# AfternoonCape_RevA3_6chan.net
KiCad netlist of a schematic drawn in Altium Designer
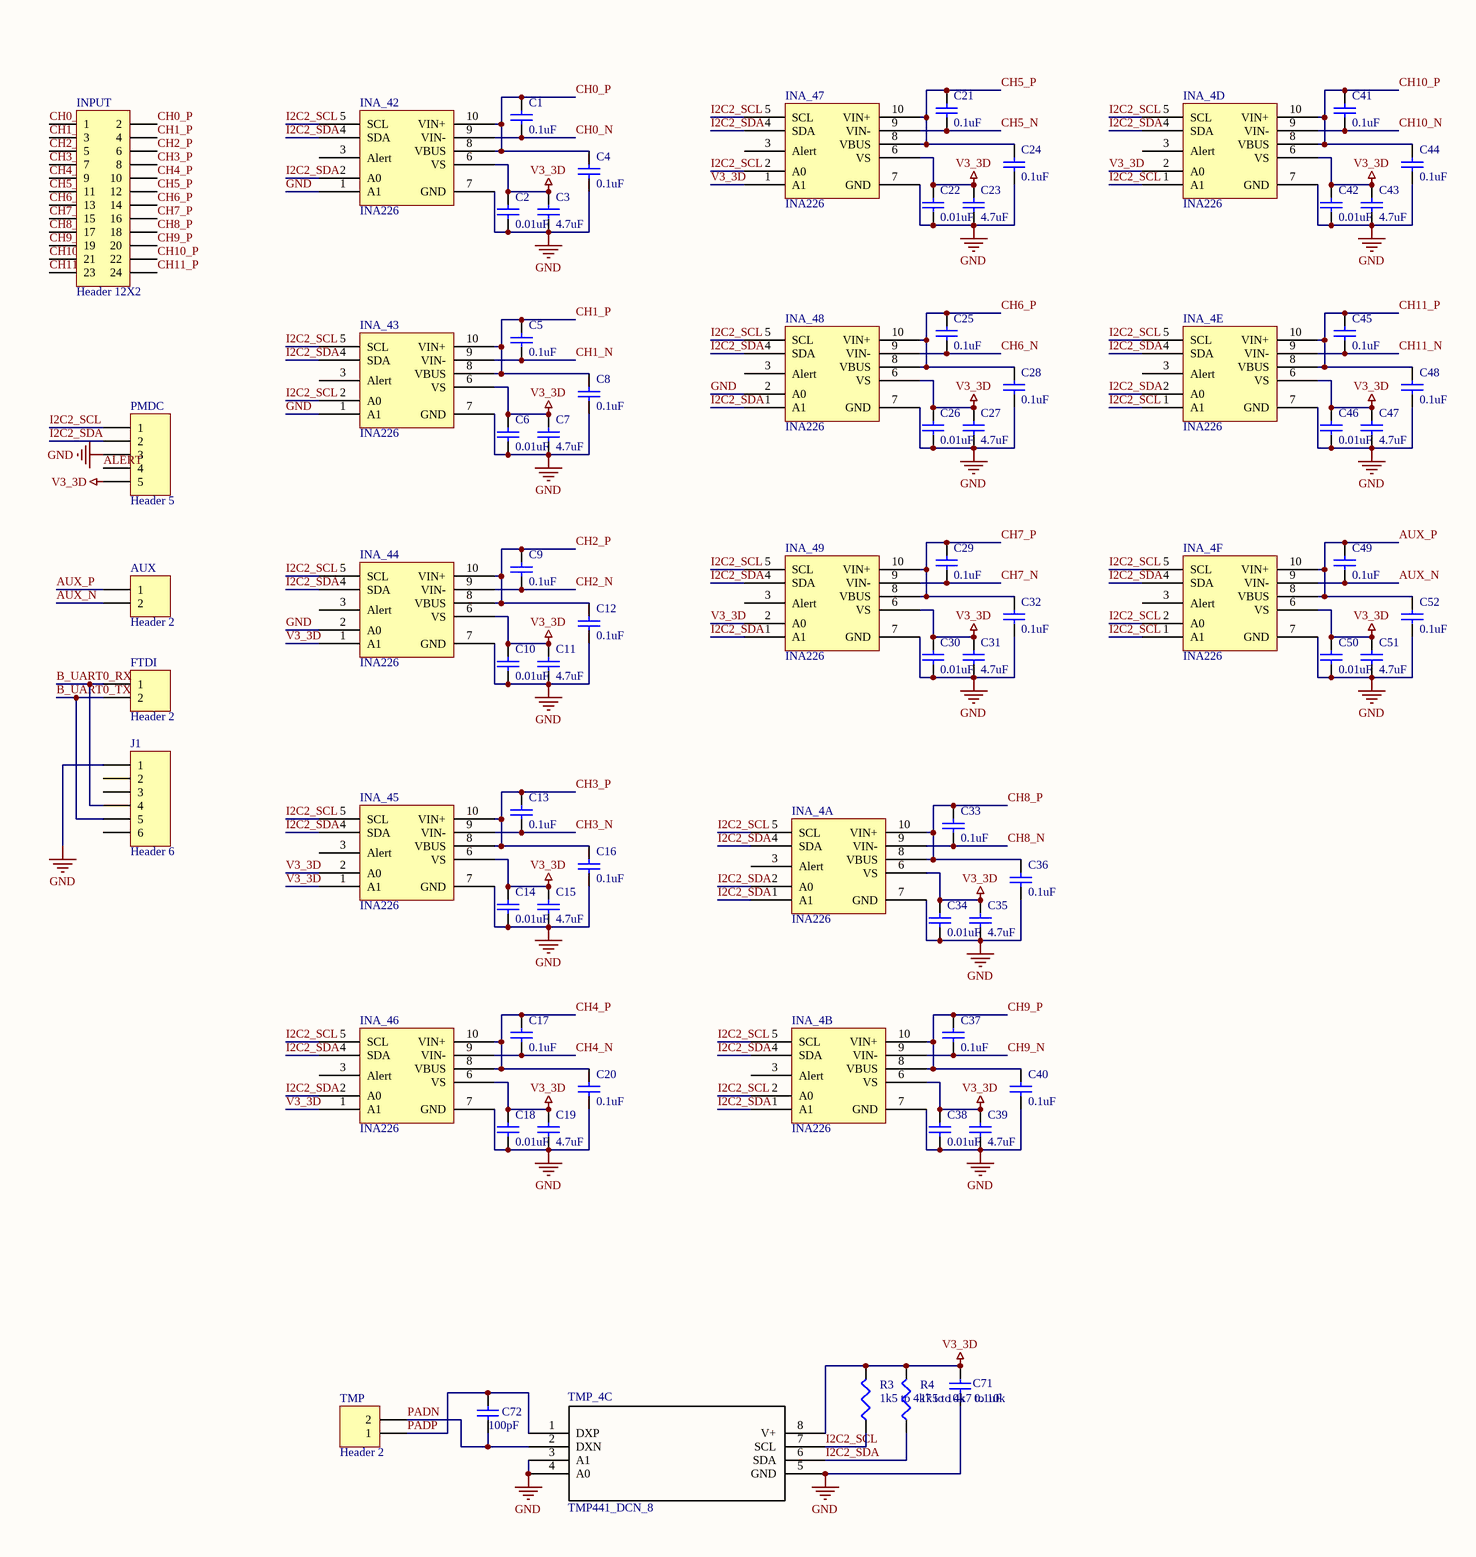
[diagram p0: AfternoonCape_RevA3_6chan.SchDoc, left]
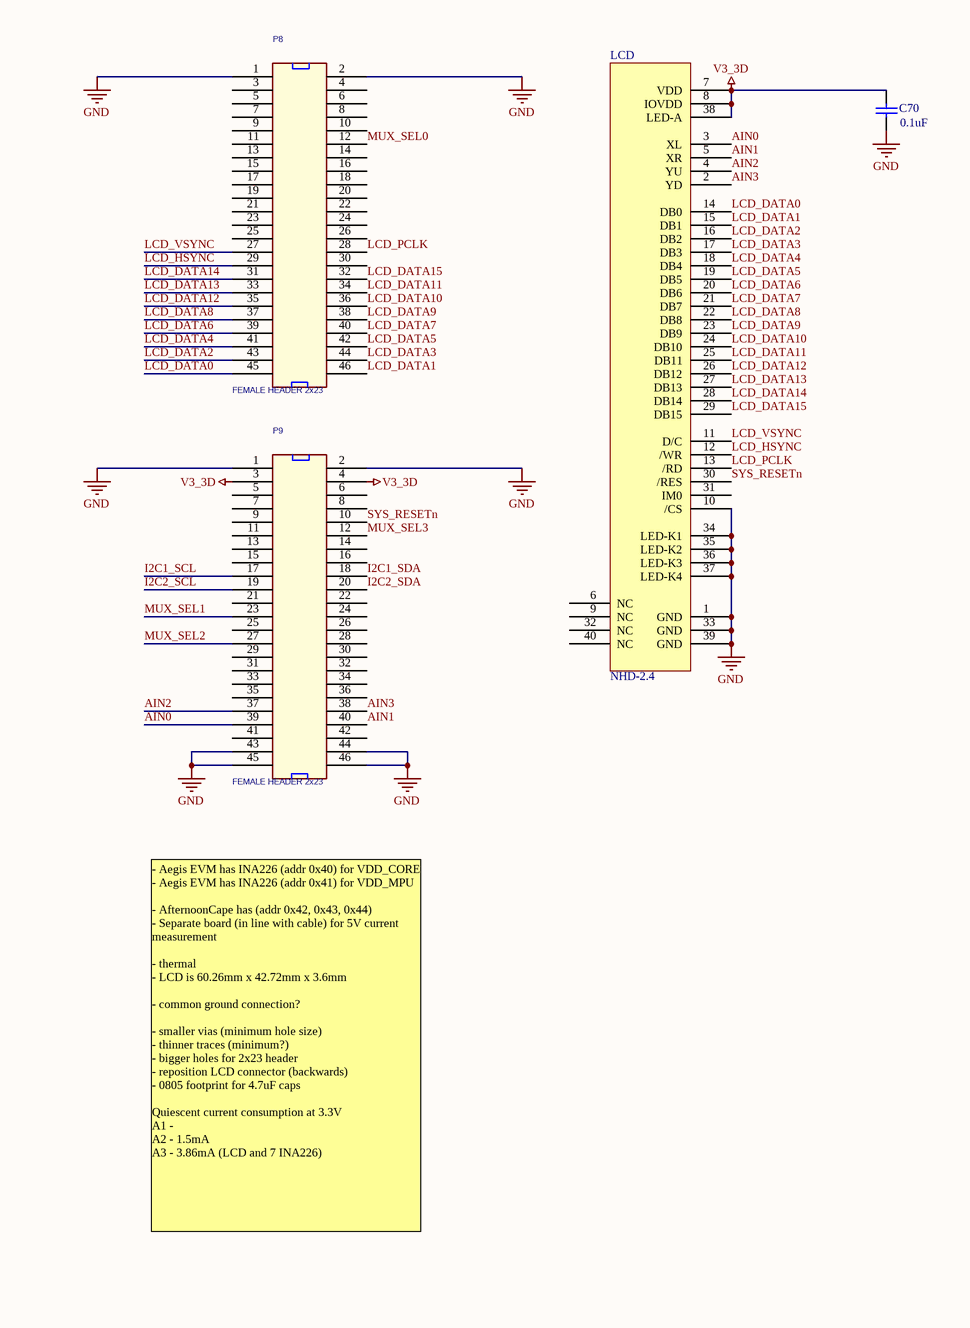
[diagram p1: AfternoonCape_RevA3_6chan.SchDoc, right]

(export (version "E")
  (design (tool "Eeschema 10.0.6"))
  (components
    (comp (ref "AUX")
      (value "Header 2")
      (footprint "HDR1X2")
      (description "Header, 2-Pin")
      (fields (field (name "PUBLISHER") "Altium Limited"))
      (libsource (lib "") (part "Header 2_1"))
    )
    (comp (ref "C1")
      (value "0.1uF")
      (footprint "0402")
      (description "Capacitor (Semiconductor SIM Model)")
      (fields (field (name "Comment") "Cap Semi") (field (name "PUBLISHER") "Altium Limited"))
      (libsource (lib "Miscellaneous Devices") (part "Cap Semi"))
    )
    (comp (ref "C2")
      (value "0.01uF")
      (footprint "0402")
      (description "Capacitor (Semiconductor SIM Model)")
      (fields (field (name "Comment") "Cap Semi") (field (name "PUBLISHER") "Altium Limited"))
      (libsource (lib "Miscellaneous Devices") (part "Cap Semi"))
    )
    (comp (ref "C3")
      (value "4.7uF")
      (footprint "0402")
      (description "Capacitor (Semiconductor SIM Model)")
      (fields (field (name "Comment") "Cap Semi") (field (name "PUBLISHER") "Altium Limited"))
      (libsource (lib "Miscellaneous Devices") (part "Cap Semi"))
    )
    (comp (ref "C4")
      (value "0.1uF")
      (footprint "0402")
      (description "Capacitor (Semiconductor SIM Model)")
      (fields (field (name "Comment") "Cap Semi") (field (name "PUBLISHER") "Altium Limited"))
      (libsource (lib "Miscellaneous Devices") (part "Cap Semi"))
    )
    (comp (ref "C5")
      (value "0.1uF")
      (footprint "0402")
      (description "Capacitor (Semiconductor SIM Model)")
      (fields (field (name "Comment") "Cap Semi") (field (name "PUBLISHER") "Altium Limited"))
      (libsource (lib "Miscellaneous Devices") (part "Cap Semi"))
    )
    (comp (ref "C6")
      (value "0.01uF")
      (footprint "0402")
      (description "Capacitor (Semiconductor SIM Model)")
      (fields (field (name "Comment") "Cap Semi") (field (name "PUBLISHER") "Altium Limited"))
      (libsource (lib "Miscellaneous Devices") (part "Cap Semi"))
    )
    (comp (ref "C7")
      (value "4.7uF")
      (footprint "0402")
      (description "Capacitor (Semiconductor SIM Model)")
      (fields (field (name "Comment") "Cap Semi") (field (name "PUBLISHER") "Altium Limited"))
      (libsource (lib "Miscellaneous Devices") (part "Cap Semi"))
    )
    (comp (ref "C8")
      (value "0.1uF")
      (footprint "0402")
      (description "Capacitor (Semiconductor SIM Model)")
      (fields (field (name "Comment") "Cap Semi") (field (name "PUBLISHER") "Altium Limited"))
      (libsource (lib "Miscellaneous Devices") (part "Cap Semi"))
    )
    (comp (ref "C9")
      (value "0.1uF")
      (footprint "0402")
      (description "Capacitor (Semiconductor SIM Model)")
      (fields (field (name "Comment") "Cap Semi") (field (name "PUBLISHER") "Altium Limited"))
      (libsource (lib "Miscellaneous Devices") (part "Cap Semi"))
    )
    (comp (ref "C10")
      (value "0.01uF")
      (footprint "0402")
      (description "Capacitor (Semiconductor SIM Model)")
      (fields (field (name "Comment") "Cap Semi") (field (name "PUBLISHER") "Altium Limited"))
      (libsource (lib "Miscellaneous Devices") (part "Cap Semi"))
    )
    (comp (ref "C11")
      (value "4.7uF")
      (footprint "0402")
      (description "Capacitor (Semiconductor SIM Model)")
      (fields (field (name "Comment") "Cap Semi") (field (name "PUBLISHER") "Altium Limited"))
      (libsource (lib "Miscellaneous Devices") (part "Cap Semi"))
    )
    (comp (ref "C12")
      (value "0.1uF")
      (footprint "0402")
      (description "Capacitor (Semiconductor SIM Model)")
      (fields (field (name "Comment") "Cap Semi") (field (name "PUBLISHER") "Altium Limited"))
      (libsource (lib "Miscellaneous Devices") (part "Cap Semi"))
    )
    (comp (ref "C13")
      (value "0.1uF")
      (footprint "0402")
      (description "Capacitor (Semiconductor SIM Model)")
      (fields (field (name "Comment") "Cap Semi") (field (name "PUBLISHER") "Altium Limited"))
      (libsource (lib "Miscellaneous Devices") (part "Cap Semi"))
    )
    (comp (ref "C14")
      (value "0.01uF")
      (footprint "0402")
      (description "Capacitor (Semiconductor SIM Model)")
      (fields (field (name "Comment") "Cap Semi") (field (name "PUBLISHER") "Altium Limited"))
      (libsource (lib "Miscellaneous Devices") (part "Cap Semi"))
    )
    (comp (ref "C15")
      (value "4.7uF")
      (footprint "0402")
      (description "Capacitor (Semiconductor SIM Model)")
      (fields (field (name "Comment") "Cap Semi") (field (name "PUBLISHER") "Altium Limited"))
      (libsource (lib "Miscellaneous Devices") (part "Cap Semi"))
    )
    (comp (ref "C16")
      (value "0.1uF")
      (footprint "0402")
      (description "Capacitor (Semiconductor SIM Model)")
      (fields (field (name "Comment") "Cap Semi") (field (name "PUBLISHER") "Altium Limited"))
      (libsource (lib "Miscellaneous Devices") (part "Cap Semi"))
    )
    (comp (ref "C17")
      (value "0.1uF")
      (footprint "0402")
      (description "Capacitor (Semiconductor SIM Model)")
      (fields (field (name "Comment") "Cap Semi") (field (name "PUBLISHER") "Altium Limited"))
      (libsource (lib "Miscellaneous Devices") (part "Cap Semi"))
    )
    (comp (ref "C18")
      (value "0.01uF")
      (footprint "0402")
      (description "Capacitor (Semiconductor SIM Model)")
      (fields (field (name "Comment") "Cap Semi") (field (name "PUBLISHER") "Altium Limited"))
      (libsource (lib "Miscellaneous Devices") (part "Cap Semi"))
    )
    (comp (ref "C19")
      (value "4.7uF")
      (footprint "0402")
      (description "Capacitor (Semiconductor SIM Model)")
      (fields (field (name "Comment") "Cap Semi") (field (name "PUBLISHER") "Altium Limited"))
      (libsource (lib "Miscellaneous Devices") (part "Cap Semi"))
    )
    (comp (ref "C20")
      (value "0.1uF")
      (footprint "0402")
      (description "Capacitor (Semiconductor SIM Model)")
      (fields (field (name "Comment") "Cap Semi") (field (name "PUBLISHER") "Altium Limited"))
      (libsource (lib "Miscellaneous Devices") (part "Cap Semi"))
    )
    (comp (ref "C21")
      (value "0.1uF")
      (footprint "0402")
      (description "Capacitor (Semiconductor SIM Model)")
      (fields (field (name "Comment") "Cap Semi") (field (name "PUBLISHER") "Altium Limited"))
      (libsource (lib "Miscellaneous Devices") (part "Cap Semi"))
    )
    (comp (ref "C22")
      (value "0.01uF")
      (footprint "0402")
      (description "Capacitor (Semiconductor SIM Model)")
      (fields (field (name "Comment") "Cap Semi") (field (name "PUBLISHER") "Altium Limited"))
      (libsource (lib "Miscellaneous Devices") (part "Cap Semi"))
    )
    (comp (ref "C23")
      (value "4.7uF")
      (footprint "0402")
      (description "Capacitor (Semiconductor SIM Model)")
      (fields (field (name "Comment") "Cap Semi") (field (name "PUBLISHER") "Altium Limited"))
      (libsource (lib "Miscellaneous Devices") (part "Cap Semi"))
    )
    (comp (ref "C24")
      (value "0.1uF")
      (footprint "0402")
      (description "Capacitor (Semiconductor SIM Model)")
      (fields (field (name "Comment") "Cap Semi") (field (name "PUBLISHER") "Altium Limited"))
      (libsource (lib "Miscellaneous Devices") (part "Cap Semi"))
    )
    (comp (ref "C25")
      (value "0.1uF")
      (footprint "0402")
      (description "Capacitor (Semiconductor SIM Model)")
      (fields (field (name "Comment") "Cap Semi") (field (name "PUBLISHER") "Altium Limited"))
      (libsource (lib "Miscellaneous Devices") (part "Cap Semi"))
    )
    (comp (ref "C26")
      (value "0.01uF")
      (footprint "0402")
      (description "Capacitor (Semiconductor SIM Model)")
      (fields (field (name "Comment") "Cap Semi") (field (name "PUBLISHER") "Altium Limited"))
      (libsource (lib "Miscellaneous Devices") (part "Cap Semi"))
    )
    (comp (ref "C27")
      (value "4.7uF")
      (footprint "0402")
      (description "Capacitor (Semiconductor SIM Model)")
      (fields (field (name "Comment") "Cap Semi") (field (name "PUBLISHER") "Altium Limited"))
      (libsource (lib "Miscellaneous Devices") (part "Cap Semi"))
    )
    (comp (ref "C28")
      (value "0.1uF")
      (footprint "0402")
      (description "Capacitor (Semiconductor SIM Model)")
      (fields (field (name "Comment") "Cap Semi") (field (name "PUBLISHER") "Altium Limited"))
      (libsource (lib "Miscellaneous Devices") (part "Cap Semi"))
    )
    (comp (ref "C29")
      (value "0.1uF")
      (footprint "0402")
      (description "Capacitor (Semiconductor SIM Model)")
      (fields (field (name "Comment") "Cap Semi") (field (name "PUBLISHER") "Altium Limited"))
      (libsource (lib "Miscellaneous Devices") (part "Cap Semi"))
    )
    (comp (ref "C30")
      (value "0.01uF")
      (footprint "0402")
      (description "Capacitor (Semiconductor SIM Model)")
      (fields (field (name "Comment") "Cap Semi") (field (name "PUBLISHER") "Altium Limited"))
      (libsource (lib "Miscellaneous Devices") (part "Cap Semi"))
    )
    (comp (ref "C31")
      (value "4.7uF")
      (footprint "0402")
      (description "Capacitor (Semiconductor SIM Model)")
      (fields (field (name "Comment") "Cap Semi") (field (name "PUBLISHER") "Altium Limited"))
      (libsource (lib "Miscellaneous Devices") (part "Cap Semi"))
    )
    (comp (ref "C32")
      (value "0.1uF")
      (footprint "0402")
      (description "Capacitor (Semiconductor SIM Model)")
      (fields (field (name "Comment") "Cap Semi") (field (name "PUBLISHER") "Altium Limited"))
      (libsource (lib "Miscellaneous Devices") (part "Cap Semi"))
    )
    (comp (ref "C33")
      (value "0.1uF")
      (footprint "0402")
      (description "Capacitor (Semiconductor SIM Model)")
      (fields (field (name "Comment") "Cap Semi") (field (name "PUBLISHER") "Altium Limited"))
      (libsource (lib "Miscellaneous Devices") (part "Cap Semi"))
    )
    (comp (ref "C34")
      (value "0.01uF")
      (footprint "0402")
      (description "Capacitor (Semiconductor SIM Model)")
      (fields (field (name "Comment") "Cap Semi") (field (name "PUBLISHER") "Altium Limited"))
      (libsource (lib "Miscellaneous Devices") (part "Cap Semi"))
    )
    (comp (ref "C35")
      (value "4.7uF")
      (footprint "0402")
      (description "Capacitor (Semiconductor SIM Model)")
      (fields (field (name "Comment") "Cap Semi") (field (name "PUBLISHER") "Altium Limited"))
      (libsource (lib "Miscellaneous Devices") (part "Cap Semi"))
    )
    (comp (ref "C36")
      (value "0.1uF")
      (footprint "0402")
      (description "Capacitor (Semiconductor SIM Model)")
      (fields (field (name "Comment") "Cap Semi") (field (name "PUBLISHER") "Altium Limited"))
      (libsource (lib "Miscellaneous Devices") (part "Cap Semi"))
    )
    (comp (ref "C37")
      (value "0.1uF")
      (footprint "0402")
      (description "Capacitor (Semiconductor SIM Model)")
      (fields (field (name "Comment") "Cap Semi") (field (name "PUBLISHER") "Altium Limited"))
      (libsource (lib "Miscellaneous Devices") (part "Cap Semi"))
    )
    (comp (ref "C38")
      (value "0.01uF")
      (footprint "0402")
      (description "Capacitor (Semiconductor SIM Model)")
      (fields (field (name "Comment") "Cap Semi") (field (name "PUBLISHER") "Altium Limited"))
      (libsource (lib "Miscellaneous Devices") (part "Cap Semi"))
    )
    (comp (ref "C39")
      (value "4.7uF")
      (footprint "0402")
      (description "Capacitor (Semiconductor SIM Model)")
      (fields (field (name "Comment") "Cap Semi") (field (name "PUBLISHER") "Altium Limited"))
      (libsource (lib "Miscellaneous Devices") (part "Cap Semi"))
    )
    (comp (ref "C40")
      (value "0.1uF")
      (footprint "0402")
      (description "Capacitor (Semiconductor SIM Model)")
      (fields (field (name "Comment") "Cap Semi") (field (name "PUBLISHER") "Altium Limited"))
      (libsource (lib "Miscellaneous Devices") (part "Cap Semi"))
    )
    (comp (ref "C41")
      (value "0.1uF")
      (footprint "0402")
      (description "Capacitor (Semiconductor SIM Model)")
      (fields (field (name "Comment") "Cap Semi") (field (name "PUBLISHER") "Altium Limited"))
      (libsource (lib "Miscellaneous Devices") (part "Cap Semi"))
    )
    (comp (ref "C42")
      (value "0.01uF")
      (footprint "0402")
      (description "Capacitor (Semiconductor SIM Model)")
      (fields (field (name "Comment") "Cap Semi") (field (name "PUBLISHER") "Altium Limited"))
      (libsource (lib "Miscellaneous Devices") (part "Cap Semi"))
    )
    (comp (ref "C43")
      (value "4.7uF")
      (footprint "0402")
      (description "Capacitor (Semiconductor SIM Model)")
      (fields (field (name "Comment") "Cap Semi") (field (name "PUBLISHER") "Altium Limited"))
      (libsource (lib "Miscellaneous Devices") (part "Cap Semi"))
    )
    (comp (ref "C44")
      (value "0.1uF")
      (footprint "0402")
      (description "Capacitor (Semiconductor SIM Model)")
      (fields (field (name "Comment") "Cap Semi") (field (name "PUBLISHER") "Altium Limited"))
      (libsource (lib "Miscellaneous Devices") (part "Cap Semi"))
    )
    (comp (ref "C45")
      (value "0.1uF")
      (footprint "0402")
      (description "Capacitor (Semiconductor SIM Model)")
      (fields (field (name "Comment") "Cap Semi") (field (name "PUBLISHER") "Altium Limited"))
      (libsource (lib "Miscellaneous Devices") (part "Cap Semi"))
    )
    (comp (ref "C46")
      (value "0.01uF")
      (footprint "0402")
      (description "Capacitor (Semiconductor SIM Model)")
      (fields (field (name "Comment") "Cap Semi") (field (name "PUBLISHER") "Altium Limited"))
      (libsource (lib "Miscellaneous Devices") (part "Cap Semi"))
    )
    (comp (ref "C47")
      (value "4.7uF")
      (footprint "0402")
      (description "Capacitor (Semiconductor SIM Model)")
      (fields (field (name "Comment") "Cap Semi") (field (name "PUBLISHER") "Altium Limited"))
      (libsource (lib "Miscellaneous Devices") (part "Cap Semi"))
    )
    (comp (ref "C48")
      (value "0.1uF")
      (footprint "0402")
      (description "Capacitor (Semiconductor SIM Model)")
      (fields (field (name "Comment") "Cap Semi") (field (name "PUBLISHER") "Altium Limited"))
      (libsource (lib "Miscellaneous Devices") (part "Cap Semi"))
    )
    (comp (ref "C49")
      (value "0.1uF")
      (footprint "0402")
      (description "Capacitor (Semiconductor SIM Model)")
      (fields (field (name "Comment") "Cap Semi") (field (name "PUBLISHER") "Altium Limited"))
      (libsource (lib "Miscellaneous Devices") (part "Cap Semi"))
    )
    (comp (ref "C50")
      (value "0.01uF")
      (footprint "0402")
      (description "Capacitor (Semiconductor SIM Model)")
      (fields (field (name "Comment") "Cap Semi") (field (name "PUBLISHER") "Altium Limited"))
      (libsource (lib "Miscellaneous Devices") (part "Cap Semi"))
    )
    (comp (ref "C51")
      (value "4.7uF")
      (footprint "0402")
      (description "Capacitor (Semiconductor SIM Model)")
      (fields (field (name "Comment") "Cap Semi") (field (name "PUBLISHER") "Altium Limited"))
      (libsource (lib "Miscellaneous Devices") (part "Cap Semi"))
    )
    (comp (ref "C52")
      (value "0.1uF")
      (footprint "0402")
      (description "Capacitor (Semiconductor SIM Model)")
      (fields (field (name "Comment") "Cap Semi") (field (name "PUBLISHER") "Altium Limited"))
      (libsource (lib "Miscellaneous Devices") (part "Cap Semi"))
    )
    (comp (ref "C70")
      (value "0.1uF")
      (footprint "0402")
      (description "Capacitor (Semiconductor SIM Model)")
      (fields (field (name "Comment") "Cap Semi") (field (name "PUBLISHER") "Altium Limited"))
      (libsource (lib "Miscellaneous Devices") (part "Cap Semi"))
    )
    (comp (ref "C71")
      (value "0.1uF")
      (footprint "0402")
      (description "Capacitor (Semiconductor SIM Model)")
      (fields (field (name "Comment") "Cap Semi") (field (name "PUBLISHER") "Altium Limited"))
      (libsource (lib "Miscellaneous Devices") (part "Cap Semi"))
    )
    (comp (ref "C72")
      (value "100pF")
      (footprint "0402")
      (description "Capacitor (Semiconductor SIM Model)")
      (fields (field (name "Comment") "Cap Semi") (field (name "PUBLISHER") "Altium Limited"))
      (libsource (lib "Miscellaneous Devices") (part "Cap Semi"))
    )
    (comp (ref "FTDI")
      (value "Header 2")
      (footprint "HDR1X2")
      (description "Header, 2-Pin")
      (fields (field (name "PUBLISHER") "Altium Limited"))
      (libsource (lib "") (part "Header 2_1"))
    )
    (comp (ref "INA_4A") (value "INA226") (footprint "DGS10") (libsource (lib "INA226") (part "INA226")))
    (comp (ref "INA_4B") (value "INA226") (footprint "DGS10") (libsource (lib "INA226") (part "INA226")))
    (comp (ref "INA_4D") (value "INA226") (footprint "DGS10") (libsource (lib "INA226") (part "INA226")))
    (comp (ref "INA_4E") (value "INA226") (footprint "DGS10") (libsource (lib "INA226") (part "INA226")))
    (comp (ref "INA_4F") (value "INA226") (footprint "DGS10") (libsource (lib "INA226") (part "INA226")))
    (comp (ref "INA_42") (value "INA226") (footprint "DGS10") (libsource (lib "INA226") (part "INA226")))
    (comp (ref "INA_43") (value "INA226") (footprint "DGS10") (libsource (lib "INA226") (part "INA226")))
    (comp (ref "INA_44") (value "INA226") (footprint "DGS10") (libsource (lib "INA226") (part "INA226")))
    (comp (ref "INA_45") (value "INA226") (footprint "DGS10") (libsource (lib "INA226") (part "INA226")))
    (comp (ref "INA_46") (value "INA226") (footprint "DGS10") (libsource (lib "INA226") (part "INA226")))
    (comp (ref "INA_47") (value "INA226") (footprint "DGS10") (libsource (lib "INA226") (part "INA226")))
    (comp (ref "INA_48") (value "INA226") (footprint "DGS10") (libsource (lib "INA226") (part "INA226")))
    (comp (ref "INA_49") (value "INA226") (footprint "DGS10") (libsource (lib "INA226") (part "INA226")))
    (comp (ref "INPUT")
      (value "Header 12X2")
      (footprint "HDR2X12")
      (description "Header, 12-Pin, Dual row")
      (fields (field (name "PUBLISHER") "Altium Limited"))
      (libsource (lib "Miscellaneous Connectors") (part "Header 12X2"))
    )
    (comp (ref "J1")
      (value "Header 6")
      (footprint "HDR1X6")
      (description "6-pin female header, long legs for FTDI-USB cable")
      (fields (field (name "PUBLISHER") "Altium Limited"))
      (libsource (lib "Miscellaneous Connectors") (part "Header 6"))
    )
    (comp (ref "LCD")
      (value "NHD-2.4")
      (footprint "NHD-2.4")
      (description "2.4\" LCD NHD-2.4-240320SF-CTXL#-FTN1 54132-4062 Molex LCD Connector Footprint")
      (libsource (lib "Sitara_PowerMonitorCape") (part "NHD-2.4"))
    )
    (comp (ref "P8")
      (value "FEMALE HEADER 2x23")
      (description "CONN HEADER FMAL 46PS.1\" DL GOLD")
      (fields
        (field (name "MANUFACTURER") "Sullins Connector Solutions")
        (field (name "MANUFACTURER PART NUMBER") "PPPC232LFBN-RC")
      )
      (libsource (lib "BEAGLEBONEBLACK_REV A5B") (part "HDR_46_F_2_0.1_0.1"))
    )
    (comp (ref "P9")
      (value "FEMALE HEADER 2x23")
      (description "CONN HEADER FMAL 46PS.1\" DL GOLD")
      (fields
        (field (name "MANUFACTURER") "Sullins Connector Solutions")
        (field (name "MANUFACTURER PART NUMBER") "PPPC232LFBN-RC")
      )
      (libsource (lib "BEAGLEBONEBLACK_REV A5B") (part "HDR_46_F_2_0.1_0.1"))
    )
    (comp (ref "PMDC")
      (value "Header 5")
      (footprint "HDR1X5")
      (description "Header, 5-Pin")
      (fields (field (name "PUBLISHER") "Altium Limited"))
      (libsource (lib "Miscellaneous Connectors") (part "Header 5"))
    )
    (comp (ref "R3")
      (value "1k5 to 4k7 to 10k")
      (footprint "0402")
      (description "Resistor")
      (fields (field (name "Comment") "Res3") (field (name "PUBLISHER") "Altium Limited"))
      (libsource (lib "Miscellaneous Devices") (part "Res3"))
    )
    (comp (ref "R4")
      (value "1k5 to 4k7 to 10k")
      (footprint "0402")
      (description "Resistor")
      (fields (field (name "Comment") "Res3") (field (name "PUBLISHER") "Altium Limited"))
      (libsource (lib "Miscellaneous Devices") (part "Res3"))
    )
    (comp (ref "TMP")
      (value "Header 2")
      (footprint "HDR1X2")
      (description "Header, 2-Pin")
      (fields (field (name "PUBLISHER") "Altium Limited"))
      (libsource (lib "Miscellaneous Connectors") (part "Header 2"))
    )
    (comp (ref "TMP_4C")
      (value "TMP441_DCN_8")
      (footprint "TMP441:DCN8-L")
      (description "Imported")
      (fields
        (field (name "MANUFACTURER_PART_NUMBER") "tmp441_dcn_8")
        (field (name "GENERIC_PART_NUMBER") "TMP441")
      )
      (libsource (lib "TMP441") (part "TMP441_DCN_8"))
    )
  )
  (nets
    (net (code "1") (name "/AIN0") (class "Default")
      (node (ref "LCD") (pin "3") (pinfunction "XL_3") (pintype "passive"))
      (node (ref "P9") (pin "39") (pinfunction "20_39") (pintype "passive"))
    )
    (net (code "2") (name "/AIN1") (class "Default")
      (node (ref "LCD") (pin "5") (pinfunction "XR_5") (pintype "passive"))
      (node (ref "P9") (pin "40") (pinfunction "45_40") (pintype "passive"))
    )
    (net (code "3") (name "/AIN2") (class "Default")
      (node (ref "LCD") (pin "4") (pinfunction "YU_4") (pintype "passive"))
      (node (ref "P9") (pin "37") (pinfunction "19_37") (pintype "passive"))
    )
    (net (code "4") (name "/AIN3") (class "Default")
      (node (ref "LCD") (pin "2") (pinfunction "YD_2") (pintype "passive"))
      (node (ref "P9") (pin "38") (pinfunction "44_38") (pintype "passive"))
    )
    (net (code "5") (name "/ALERT") (class "Default")
      (node (ref "PMDC") (pin "4") (pinfunction "4_4") (pintype "passive"))
    )
    (net (code "6") (name "/AUX_N") (class "Default")
      (node (ref "AUX") (pin "2") (pinfunction "2_2") (pintype "passive"))
      (node (ref "C49") (pin "1") (pinfunction "1_1") (pintype "passive"))
      (node (ref "INA_4F") (pin "9") (pinfunction "VIN-_9") (pintype "passive"))
    )
    (net (code "7") (name "/AUX_P") (class "Default")
      (node (ref "AUX") (pin "1") (pinfunction "1_1") (pintype "passive"))
      (node (ref "C49") (pin "2") (pinfunction "2_2") (pintype "passive"))
      (node (ref "C52") (pin "2") (pinfunction "2_2") (pintype "passive"))
      (node (ref "INA_4F") (pin "10") (pinfunction "VIN+_10") (pintype "passive"))
      (node (ref "INA_4F") (pin "8") (pinfunction "VBUS_8") (pintype "passive"))
    )
    (net (code "8") (name "/B_UART0_RX") (class "Default")
      (node (ref "FTDI") (pin "1") (pinfunction "1_1") (pintype "passive"))
      (node (ref "J1") (pin "4") (pinfunction "4_4") (pintype "passive"))
    )
    (net (code "9") (name "/B_UART0_TX") (class "Default")
      (node (ref "FTDI") (pin "2") (pinfunction "2_2") (pintype "passive"))
      (node (ref "J1") (pin "5") (pinfunction "5_5") (pintype "passive"))
    )
    (net (code "10") (name "/CH0_N") (class "Default")
      (node (ref "C1") (pin "1") (pinfunction "1_1") (pintype "passive"))
      (node (ref "INA_42") (pin "9") (pinfunction "VIN-_9") (pintype "passive"))
      (node (ref "INPUT") (pin "1") (pinfunction "1_1") (pintype "passive"))
    )
    (net (code "11") (name "/CH0_P") (class "Default")
      (node (ref "C1") (pin "2") (pinfunction "2_2") (pintype "passive"))
      (node (ref "C4") (pin "2") (pinfunction "2_2") (pintype "passive"))
      (node (ref "INA_42") (pin "10") (pinfunction "VIN+_10") (pintype "passive"))
      (node (ref "INA_42") (pin "8") (pinfunction "VBUS_8") (pintype "passive"))
      (node (ref "INPUT") (pin "2") (pinfunction "2_2") (pintype "passive"))
    )
    (net (code "12") (name "/CH1_N") (class "Default")
      (node (ref "C5") (pin "1") (pinfunction "1_1") (pintype "passive"))
      (node (ref "INA_43") (pin "9") (pinfunction "VIN-_9") (pintype "passive"))
      (node (ref "INPUT") (pin "3") (pinfunction "3_3") (pintype "passive"))
    )
    (net (code "13") (name "/CH1_P") (class "Default")
      (node (ref "C5") (pin "2") (pinfunction "2_2") (pintype "passive"))
      (node (ref "C8") (pin "2") (pinfunction "2_2") (pintype "passive"))
      (node (ref "INA_43") (pin "10") (pinfunction "VIN+_10") (pintype "passive"))
      (node (ref "INA_43") (pin "8") (pinfunction "VBUS_8") (pintype "passive"))
      (node (ref "INPUT") (pin "4") (pinfunction "4_4") (pintype "passive"))
    )
    (net (code "14") (name "/CH2_N") (class "Default")
      (node (ref "C9") (pin "1") (pinfunction "1_1") (pintype "passive"))
      (node (ref "INA_44") (pin "9") (pinfunction "VIN-_9") (pintype "passive"))
      (node (ref "INPUT") (pin "5") (pinfunction "5_5") (pintype "passive"))
    )
    (net (code "15") (name "/CH2_P") (class "Default")
      (node (ref "C12") (pin "2") (pinfunction "2_2") (pintype "passive"))
      (node (ref "C9") (pin "2") (pinfunction "2_2") (pintype "passive"))
      (node (ref "INA_44") (pin "10") (pinfunction "VIN+_10") (pintype "passive"))
      (node (ref "INA_44") (pin "8") (pinfunction "VBUS_8") (pintype "passive"))
      (node (ref "INPUT") (pin "6") (pinfunction "6_6") (pintype "passive"))
    )
    (net (code "16") (name "/CH3_N") (class "Default")
      (node (ref "C13") (pin "1") (pinfunction "1_1") (pintype "passive"))
      (node (ref "INA_45") (pin "9") (pinfunction "VIN-_9") (pintype "passive"))
      (node (ref "INPUT") (pin "7") (pinfunction "7_7") (pintype "passive"))
    )
    (net (code "17") (name "/CH3_P") (class "Default")
      (node (ref "C13") (pin "2") (pinfunction "2_2") (pintype "passive"))
      (node (ref "C16") (pin "2") (pinfunction "2_2") (pintype "passive"))
      (node (ref "INA_45") (pin "10") (pinfunction "VIN+_10") (pintype "passive"))
      (node (ref "INA_45") (pin "8") (pinfunction "VBUS_8") (pintype "passive"))
      (node (ref "INPUT") (pin "8") (pinfunction "8_8") (pintype "passive"))
    )
    (net (code "18") (name "/CH4_N") (class "Default")
      (node (ref "C17") (pin "1") (pinfunction "1_1") (pintype "passive"))
      (node (ref "INA_46") (pin "9") (pinfunction "VIN-_9") (pintype "passive"))
      (node (ref "INPUT") (pin "9") (pinfunction "9_9") (pintype "passive"))
    )
    (net (code "19") (name "/CH4_P") (class "Default")
      (node (ref "C17") (pin "2") (pinfunction "2_2") (pintype "passive"))
      (node (ref "C20") (pin "2") (pinfunction "2_2") (pintype "passive"))
      (node (ref "INA_46") (pin "10") (pinfunction "VIN+_10") (pintype "passive"))
      (node (ref "INA_46") (pin "8") (pinfunction "VBUS_8") (pintype "passive"))
      (node (ref "INPUT") (pin "10") (pinfunction "10_10") (pintype "passive"))
    )
    (net (code "20") (name "/CH5_N") (class "Default")
      (node (ref "C21") (pin "1") (pinfunction "1_1") (pintype "passive"))
      (node (ref "INA_47") (pin "9") (pinfunction "VIN-_9") (pintype "passive"))
      (node (ref "INPUT") (pin "11") (pinfunction "11_11") (pintype "passive"))
    )
    (net (code "21") (name "/CH5_P") (class "Default")
      (node (ref "C21") (pin "2") (pinfunction "2_2") (pintype "passive"))
      (node (ref "C24") (pin "2") (pinfunction "2_2") (pintype "passive"))
      (node (ref "INA_47") (pin "10") (pinfunction "VIN+_10") (pintype "passive"))
      (node (ref "INA_47") (pin "8") (pinfunction "VBUS_8") (pintype "passive"))
      (node (ref "INPUT") (pin "12") (pinfunction "12_12") (pintype "passive"))
    )
    (net (code "22") (name "/CH6_N") (class "Default")
      (node (ref "C25") (pin "1") (pinfunction "1_1") (pintype "passive"))
      (node (ref "INA_48") (pin "9") (pinfunction "VIN-_9") (pintype "passive"))
      (node (ref "INPUT") (pin "13") (pinfunction "13_13") (pintype "passive"))
    )
    (net (code "23") (name "/CH6_P") (class "Default")
      (node (ref "C25") (pin "2") (pinfunction "2_2") (pintype "passive"))
      (node (ref "C28") (pin "2") (pinfunction "2_2") (pintype "passive"))
      (node (ref "INA_48") (pin "10") (pinfunction "VIN+_10") (pintype "passive"))
      (node (ref "INA_48") (pin "8") (pinfunction "VBUS_8") (pintype "passive"))
      (node (ref "INPUT") (pin "14") (pinfunction "14_14") (pintype "passive"))
    )
    (net (code "24") (name "/CH7_N") (class "Default")
      (node (ref "C29") (pin "1") (pinfunction "1_1") (pintype "passive"))
      (node (ref "INA_49") (pin "9") (pinfunction "VIN-_9") (pintype "passive"))
      (node (ref "INPUT") (pin "15") (pinfunction "15_15") (pintype "passive"))
    )
    (net (code "25") (name "/CH7_P") (class "Default")
      (node (ref "C29") (pin "2") (pinfunction "2_2") (pintype "passive"))
      (node (ref "C32") (pin "2") (pinfunction "2_2") (pintype "passive"))
      (node (ref "INA_49") (pin "10") (pinfunction "VIN+_10") (pintype "passive"))
      (node (ref "INA_49") (pin "8") (pinfunction "VBUS_8") (pintype "passive"))
      (node (ref "INPUT") (pin "16") (pinfunction "16_16") (pintype "passive"))
    )
    (net (code "26") (name "/CH8_N") (class "Default")
      (node (ref "C33") (pin "1") (pinfunction "1_1") (pintype "passive"))
      (node (ref "INA_4A") (pin "9") (pinfunction "VIN-_9") (pintype "passive"))
      (node (ref "INPUT") (pin "17") (pinfunction "17_17") (pintype "passive"))
    )
    (net (code "27") (name "/CH8_P") (class "Default")
      (node (ref "C33") (pin "2") (pinfunction "2_2") (pintype "passive"))
      (node (ref "C36") (pin "2") (pinfunction "2_2") (pintype "passive"))
      (node (ref "INA_4A") (pin "10") (pinfunction "VIN+_10") (pintype "passive"))
      (node (ref "INA_4A") (pin "8") (pinfunction "VBUS_8") (pintype "passive"))
      (node (ref "INPUT") (pin "18") (pinfunction "18_18") (pintype "passive"))
    )
    (net (code "28") (name "/CH9_N") (class "Default")
      (node (ref "C37") (pin "1") (pinfunction "1_1") (pintype "passive"))
      (node (ref "INA_4B") (pin "9") (pinfunction "VIN-_9") (pintype "passive"))
      (node (ref "INPUT") (pin "19") (pinfunction "19_19") (pintype "passive"))
    )
    (net (code "29") (name "/CH9_P") (class "Default")
      (node (ref "C37") (pin "2") (pinfunction "2_2") (pintype "passive"))
      (node (ref "C40") (pin "2") (pinfunction "2_2") (pintype "passive"))
      (node (ref "INA_4B") (pin "10") (pinfunction "VIN+_10") (pintype "passive"))
      (node (ref "INA_4B") (pin "8") (pinfunction "VBUS_8") (pintype "passive"))
      (node (ref "INPUT") (pin "20") (pinfunction "20_20") (pintype "passive"))
    )
    (net (code "30") (name "/CH10_N") (class "Default")
      (node (ref "C41") (pin "1") (pinfunction "1_1") (pintype "passive"))
      (node (ref "INA_4D") (pin "9") (pinfunction "VIN-_9") (pintype "passive"))
      (node (ref "INPUT") (pin "21") (pinfunction "21_21") (pintype "passive"))
    )
    (net (code "31") (name "/CH10_P") (class "Default")
      (node (ref "C41") (pin "2") (pinfunction "2_2") (pintype "passive"))
      (node (ref "C44") (pin "2") (pinfunction "2_2") (pintype "passive"))
      (node (ref "INA_4D") (pin "10") (pinfunction "VIN+_10") (pintype "passive"))
      (node (ref "INA_4D") (pin "8") (pinfunction "VBUS_8") (pintype "passive"))
      (node (ref "INPUT") (pin "22") (pinfunction "22_22") (pintype "passive"))
    )
    (net (code "32") (name "/CH11_N") (class "Default")
      (node (ref "C45") (pin "1") (pinfunction "1_1") (pintype "passive"))
      (node (ref "INA_4E") (pin "9") (pinfunction "VIN-_9") (pintype "passive"))
      (node (ref "INPUT") (pin "23") (pinfunction "23_23") (pintype "passive"))
    )
    (net (code "33") (name "/CH11_P") (class "Default")
      (node (ref "C45") (pin "2") (pinfunction "2_2") (pintype "passive"))
      (node (ref "C48") (pin "2") (pinfunction "2_2") (pintype "passive"))
      (node (ref "INA_4E") (pin "10") (pinfunction "VIN+_10") (pintype "passive"))
      (node (ref "INA_4E") (pin "8") (pinfunction "VBUS_8") (pintype "passive"))
      (node (ref "INPUT") (pin "24") (pinfunction "24_24") (pintype "passive"))
    )
    (net (code "34") (name "/I2C1_SCL") (class "Default")
      (node (ref "P9") (pin "17") (pinfunction "9_17") (pintype "passive"))
    )
    (net (code "35") (name "/I2C1_SDA") (class "Default")
      (node (ref "P9") (pin "18") (pinfunction "34_18") (pintype "passive"))
    )
    (net (code "36") (name "/I2C2_SCL") (class "Default")
      (node (ref "INA_42") (pin "5") (pinfunction "SCL_5") (pintype "passive"))
      (node (ref "INA_43") (pin "2") (pinfunction "A0_2") (pintype "passive"))
      (node (ref "INA_43") (pin "5") (pinfunction "SCL_5") (pintype "passive"))
      (node (ref "INA_44") (pin "5") (pinfunction "SCL_5") (pintype "passive"))
      (node (ref "INA_45") (pin "5") (pinfunction "SCL_5") (pintype "passive"))
      (node (ref "INA_46") (pin "5") (pinfunction "SCL_5") (pintype "passive"))
      (node (ref "INA_47") (pin "2") (pinfunction "A0_2") (pintype "passive"))
      (node (ref "INA_47") (pin "5") (pinfunction "SCL_5") (pintype "passive"))
      (node (ref "INA_48") (pin "5") (pinfunction "SCL_5") (pintype "passive"))
      (node (ref "INA_49") (pin "5") (pinfunction "SCL_5") (pintype "passive"))
      (node (ref "INA_4A") (pin "5") (pinfunction "SCL_5") (pintype "passive"))
      (node (ref "INA_4B") (pin "2") (pinfunction "A0_2") (pintype "passive"))
      (node (ref "INA_4B") (pin "5") (pinfunction "SCL_5") (pintype "passive"))
      (node (ref "INA_4D") (pin "1") (pinfunction "A1_1") (pintype "passive"))
      (node (ref "INA_4D") (pin "5") (pinfunction "SCL_5") (pintype "passive"))
      (node (ref "INA_4E") (pin "1") (pinfunction "A1_1") (pintype "passive"))
      (node (ref "INA_4E") (pin "5") (pinfunction "SCL_5") (pintype "passive"))
      (node (ref "INA_4F") (pin "1") (pinfunction "A1_1") (pintype "passive"))
      (node (ref "INA_4F") (pin "2") (pinfunction "A0_2") (pintype "passive"))
      (node (ref "INA_4F") (pin "5") (pinfunction "SCL_5") (pintype "passive"))
      (node (ref "P9") (pin "19") (pinfunction "10_19") (pintype "passive"))
      (node (ref "PMDC") (pin "1") (pinfunction "1_1") (pintype "passive"))
      (node (ref "R3") (pin "1") (pinfunction "1_1") (pintype "passive"))
      (node (ref "TMP_4C") (pin "7") (pinfunction "SCL_7") (pintype "passive"))
    )
    (net (code "37") (name "/I2C2_SDA") (class "Default")
      (node (ref "INA_42") (pin "2") (pinfunction "A0_2") (pintype "passive"))
      (node (ref "INA_42") (pin "4") (pinfunction "SDA_4") (pintype "passive"))
      (node (ref "INA_43") (pin "4") (pinfunction "SDA_4") (pintype "passive"))
      (node (ref "INA_44") (pin "4") (pinfunction "SDA_4") (pintype "passive"))
      (node (ref "INA_45") (pin "4") (pinfunction "SDA_4") (pintype "passive"))
      (node (ref "INA_46") (pin "2") (pinfunction "A0_2") (pintype "passive"))
      (node (ref "INA_46") (pin "4") (pinfunction "SDA_4") (pintype "passive"))
      (node (ref "INA_47") (pin "4") (pinfunction "SDA_4") (pintype "passive"))
      (node (ref "INA_48") (pin "1") (pinfunction "A1_1") (pintype "passive"))
      (node (ref "INA_48") (pin "4") (pinfunction "SDA_4") (pintype "passive"))
      (node (ref "INA_49") (pin "1") (pinfunction "A1_1") (pintype "passive"))
      (node (ref "INA_49") (pin "4") (pinfunction "SDA_4") (pintype "passive"))
      (node (ref "INA_4A") (pin "1") (pinfunction "A1_1") (pintype "passive"))
      (node (ref "INA_4A") (pin "2") (pinfunction "A0_2") (pintype "passive"))
      (node (ref "INA_4A") (pin "4") (pinfunction "SDA_4") (pintype "passive"))
      (node (ref "INA_4B") (pin "1") (pinfunction "A1_1") (pintype "passive"))
      (node (ref "INA_4B") (pin "4") (pinfunction "SDA_4") (pintype "passive"))
      (node (ref "INA_4D") (pin "4") (pinfunction "SDA_4") (pintype "passive"))
      (node (ref "INA_4E") (pin "2") (pinfunction "A0_2") (pintype "passive"))
      (node (ref "INA_4E") (pin "4") (pinfunction "SDA_4") (pintype "passive"))
      (node (ref "INA_4F") (pin "4") (pinfunction "SDA_4") (pintype "passive"))
      (node (ref "P9") (pin "20") (pinfunction "35_20") (pintype "passive"))
      (node (ref "PMDC") (pin "2") (pinfunction "2_2") (pintype "passive"))
      (node (ref "R4") (pin "1") (pinfunction "1_1") (pintype "passive"))
      (node (ref "TMP_4C") (pin "6") (pinfunction "SDA_6") (pintype "passive"))
    )
    (net (code "38") (name "/LCD_DATA0") (class "Default")
      (node (ref "LCD") (pin "14") (pinfunction "DB0_14") (pintype "passive"))
      (node (ref "P8") (pin "45") (pinfunction "23_45") (pintype "passive"))
    )
    (net (code "39") (name "/LCD_DATA1") (class "Default")
      (node (ref "LCD") (pin "15") (pinfunction "DB1_15") (pintype "passive"))
      (node (ref "P8") (pin "46") (pinfunction "48_46") (pintype "passive"))
    )
    (net (code "40") (name "/LCD_DATA2") (class "Default")
      (node (ref "LCD") (pin "16") (pinfunction "DB2_16") (pintype "passive"))
      (node (ref "P8") (pin "43") (pinfunction "22_43") (pintype "passive"))
    )
    (net (code "41") (name "/LCD_DATA3") (class "Default")
      (node (ref "LCD") (pin "17") (pinfunction "DB3_17") (pintype "passive"))
      (node (ref "P8") (pin "44") (pinfunction "47_44") (pintype "passive"))
    )
    (net (code "42") (name "/LCD_DATA4") (class "Default")
      (node (ref "LCD") (pin "18") (pinfunction "DB4_18") (pintype "passive"))
      (node (ref "P8") (pin "41") (pinfunction "21_41") (pintype "passive"))
    )
    (net (code "43") (name "/LCD_DATA5") (class "Default")
      (node (ref "LCD") (pin "19") (pinfunction "DB5_19") (pintype "passive"))
      (node (ref "P8") (pin "42") (pinfunction "46_42") (pintype "passive"))
    )
    (net (code "44") (name "/LCD_DATA6") (class "Default")
      (node (ref "LCD") (pin "20") (pinfunction "DB6_20") (pintype "passive"))
      (node (ref "P8") (pin "39") (pinfunction "20_39") (pintype "passive"))
    )
    (net (code "45") (name "/LCD_DATA7") (class "Default")
      (node (ref "LCD") (pin "21") (pinfunction "DB7_21") (pintype "passive"))
      (node (ref "P8") (pin "40") (pinfunction "45_40") (pintype "passive"))
    )
    (net (code "46") (name "/LCD_DATA8") (class "Default")
      (node (ref "LCD") (pin "22") (pinfunction "DB8_22") (pintype "passive"))
      (node (ref "P8") (pin "37") (pinfunction "19_37") (pintype "passive"))
    )
    (net (code "47") (name "/LCD_DATA9") (class "Default")
      (node (ref "LCD") (pin "23") (pinfunction "DB9_23") (pintype "passive"))
      (node (ref "P8") (pin "38") (pinfunction "44_38") (pintype "passive"))
    )
    (net (code "48") (name "/LCD_DATA10") (class "Default")
      (node (ref "LCD") (pin "24") (pinfunction "DB10_24") (pintype "passive"))
      (node (ref "P8") (pin "36") (pinfunction "43_36") (pintype "passive"))
    )
    (net (code "49") (name "/LCD_DATA11") (class "Default")
      (node (ref "LCD") (pin "25") (pinfunction "DB11_25") (pintype "passive"))
      (node (ref "P8") (pin "34") (pinfunction "42_34") (pintype "passive"))
    )
    (net (code "50") (name "/LCD_DATA12") (class "Default")
      (node (ref "LCD") (pin "26") (pinfunction "DB12_26") (pintype "passive"))
      (node (ref "P8") (pin "35") (pinfunction "18_35") (pintype "passive"))
    )
    (net (code "51") (name "/LCD_DATA13") (class "Default")
      (node (ref "LCD") (pin "27") (pinfunction "DB13_27") (pintype "passive"))
      (node (ref "P8") (pin "33") (pinfunction "17_33") (pintype "passive"))
    )
    (net (code "52") (name "/LCD_DATA14") (class "Default")
      (node (ref "LCD") (pin "28") (pinfunction "DB14_28") (pintype "passive"))
      (node (ref "P8") (pin "31") (pinfunction "16_31") (pintype "passive"))
    )
    (net (code "53") (name "/LCD_DATA15") (class "Default")
      (node (ref "LCD") (pin "29") (pinfunction "DB15_29") (pintype "passive"))
      (node (ref "P8") (pin "32") (pinfunction "41_32") (pintype "passive"))
    )
    (net (code "54") (name "/LCD_HSYNC") (class "Default")
      (node (ref "LCD") (pin "12") (pinfunction "/WR_12") (pintype "passive"))
      (node (ref "P8") (pin "29") (pinfunction "15_29") (pintype "passive"))
    )
    (net (code "55") (name "/LCD_PCLK") (class "Default")
      (node (ref "LCD") (pin "13") (pinfunction "/RD_13") (pintype "passive"))
      (node (ref "P8") (pin "28") (pinfunction "39_28") (pintype "passive"))
    )
    (net (code "56") (name "/LCD_VSYNC") (class "Default")
      (node (ref "LCD") (pin "11") (pinfunction "D/C_11") (pintype "passive"))
      (node (ref "P8") (pin "27") (pinfunction "14_27") (pintype "passive"))
    )
    (net (code "57") (name "/MUX_SEL0") (class "Default")
      (node (ref "P8") (pin "12") (pinfunction "31_12") (pintype "passive"))
    )
    (net (code "58") (name "/MUX_SEL1") (class "Default")
      (node (ref "P9") (pin "23") (pinfunction "12_23") (pintype "passive"))
    )
    (net (code "59") (name "/MUX_SEL2") (class "Default")
      (node (ref "P9") (pin "27") (pinfunction "14_27") (pintype "passive"))
    )
    (net (code "60") (name "/MUX_SEL3") (class "Default")
      (node (ref "P9") (pin "12") (pinfunction "31_12") (pintype "passive"))
    )
    (net (code "61") (name "/PADN") (class "Default")
      (node (ref "C72") (pin "1") (pinfunction "1_1") (pintype "passive"))
      (node (ref "TMP") (pin "2") (pinfunction "2_2") (pintype "passive"))
      (node (ref "TMP_4C") (pin "2") (pinfunction "DXN_2") (pintype "passive"))
    )
    (net (code "62") (name "/PADP") (class "Default")
      (node (ref "C72") (pin "2") (pinfunction "2_2") (pintype "passive"))
      (node (ref "TMP") (pin "1") (pinfunction "1_1") (pintype "passive"))
      (node (ref "TMP_4C") (pin "1") (pinfunction "DXP_1") (pintype "passive"))
    )
    (net (code "63") (name "/SYS_RESETn") (class "Default")
      (node (ref "LCD") (pin "30") (pinfunction "/RES_30") (pintype "passive"))
      (node (ref "P9") (pin "10") (pinfunction "30_10") (pintype "passive"))
    )
    (net (code "64") (name "GND") (class "Default")
      (node (ref "C10") (pin "1") (pinfunction "1_1") (pintype "passive"))
      (node (ref "C11") (pin "1") (pinfunction "1_1") (pintype "passive"))
      (node (ref "C12") (pin "1") (pinfunction "1_1") (pintype "passive"))
      (node (ref "C14") (pin "1") (pinfunction "1_1") (pintype "passive"))
      (node (ref "C15") (pin "1") (pinfunction "1_1") (pintype "passive"))
      (node (ref "C16") (pin "1") (pinfunction "1_1") (pintype "passive"))
      (node (ref "C18") (pin "1") (pinfunction "1_1") (pintype "passive"))
      (node (ref "C19") (pin "1") (pinfunction "1_1") (pintype "passive"))
      (node (ref "C2") (pin "1") (pinfunction "1_1") (pintype "passive"))
      (node (ref "C20") (pin "1") (pinfunction "1_1") (pintype "passive"))
      (node (ref "C22") (pin "1") (pinfunction "1_1") (pintype "passive"))
      (node (ref "C23") (pin "1") (pinfunction "1_1") (pintype "passive"))
      (node (ref "C24") (pin "1") (pinfunction "1_1") (pintype "passive"))
      (node (ref "C26") (pin "1") (pinfunction "1_1") (pintype "passive"))
      (node (ref "C27") (pin "1") (pinfunction "1_1") (pintype "passive"))
      (node (ref "C28") (pin "1") (pinfunction "1_1") (pintype "passive"))
      (node (ref "C3") (pin "1") (pinfunction "1_1") (pintype "passive"))
      (node (ref "C30") (pin "1") (pinfunction "1_1") (pintype "passive"))
      (node (ref "C31") (pin "1") (pinfunction "1_1") (pintype "passive"))
      (node (ref "C32") (pin "1") (pinfunction "1_1") (pintype "passive"))
      (node (ref "C34") (pin "1") (pinfunction "1_1") (pintype "passive"))
      (node (ref "C35") (pin "1") (pinfunction "1_1") (pintype "passive"))
      (node (ref "C36") (pin "1") (pinfunction "1_1") (pintype "passive"))
      (node (ref "C38") (pin "1") (pinfunction "1_1") (pintype "passive"))
      (node (ref "C39") (pin "1") (pinfunction "1_1") (pintype "passive"))
      (node (ref "C4") (pin "1") (pinfunction "1_1") (pintype "passive"))
      (node (ref "C40") (pin "1") (pinfunction "1_1") (pintype "passive"))
      (node (ref "C42") (pin "1") (pinfunction "1_1") (pintype "passive"))
      (node (ref "C43") (pin "1") (pinfunction "1_1") (pintype "passive"))
      (node (ref "C44") (pin "1") (pinfunction "1_1") (pintype "passive"))
      (node (ref "C46") (pin "1") (pinfunction "1_1") (pintype "passive"))
      (node (ref "C47") (pin "1") (pinfunction "1_1") (pintype "passive"))
      (node (ref "C48") (pin "1") (pinfunction "1_1") (pintype "passive"))
      (node (ref "C50") (pin "1") (pinfunction "1_1") (pintype "passive"))
      (node (ref "C51") (pin "1") (pinfunction "1_1") (pintype "passive"))
      (node (ref "C52") (pin "1") (pinfunction "1_1") (pintype "passive"))
      (node (ref "C6") (pin "1") (pinfunction "1_1") (pintype "passive"))
      (node (ref "C7") (pin "1") (pinfunction "1_1") (pintype "passive"))
      (node (ref "C70") (pin "1") (pinfunction "1_1") (pintype "passive"))
      (node (ref "C71") (pin "1") (pinfunction "1_1") (pintype "passive"))
      (node (ref "C8") (pin "1") (pinfunction "1_1") (pintype "passive"))
      (node (ref "INA_42") (pin "1") (pinfunction "A1_1") (pintype "passive"))
      (node (ref "INA_42") (pin "7") (pinfunction "GND_7") (pintype "passive"))
      (node (ref "INA_43") (pin "1") (pinfunction "A1_1") (pintype "passive"))
      (node (ref "INA_43") (pin "7") (pinfunction "GND_7") (pintype "passive"))
      (node (ref "INA_44") (pin "2") (pinfunction "A0_2") (pintype "passive"))
      (node (ref "INA_44") (pin "7") (pinfunction "GND_7") (pintype "passive"))
      (node (ref "INA_45") (pin "7") (pinfunction "GND_7") (pintype "passive"))
      (node (ref "INA_46") (pin "7") (pinfunction "GND_7") (pintype "passive"))
      (node (ref "INA_47") (pin "7") (pinfunction "GND_7") (pintype "passive"))
      (node (ref "INA_48") (pin "2") (pinfunction "A0_2") (pintype "passive"))
      (node (ref "INA_48") (pin "7") (pinfunction "GND_7") (pintype "passive"))
      (node (ref "INA_49") (pin "7") (pinfunction "GND_7") (pintype "passive"))
      (node (ref "INA_4A") (pin "7") (pinfunction "GND_7") (pintype "passive"))
      (node (ref "INA_4B") (pin "7") (pinfunction "GND_7") (pintype "passive"))
      (node (ref "INA_4D") (pin "7") (pinfunction "GND_7") (pintype "passive"))
      (node (ref "INA_4E") (pin "7") (pinfunction "GND_7") (pintype "passive"))
      (node (ref "INA_4F") (pin "7") (pinfunction "GND_7") (pintype "passive"))
      (node (ref "J1") (pin "1") (pinfunction "1_1") (pintype "passive"))
      (node (ref "LCD") (pin "1") (pinfunction "GND_1") (pintype "passive"))
      (node (ref "LCD") (pin "10") (pinfunction "/CS_10") (pintype "passive"))
      (node (ref "LCD") (pin "33") (pinfunction "GND_33") (pintype "passive"))
      (node (ref "LCD") (pin "34") (pinfunction "LED-K1_34") (pintype "passive"))
      (node (ref "LCD") (pin "35") (pinfunction "LED-K2_35") (pintype "passive"))
      (node (ref "LCD") (pin "36") (pinfunction "LED-K3_36") (pintype "passive"))
      (node (ref "LCD") (pin "37") (pinfunction "LED-K4_37") (pintype "passive"))
      (node (ref "LCD") (pin "39") (pinfunction "GND_39") (pintype "passive"))
      (node (ref "P8") (pin "1") (pinfunction "1_1") (pintype "passive"))
      (node (ref "P8") (pin "2") (pinfunction "26_2") (pintype "passive"))
      (node (ref "P9") (pin "1") (pinfunction "1_1") (pintype "passive"))
      (node (ref "P9") (pin "2") (pinfunction "26_2") (pintype "passive"))
      (node (ref "P9") (pin "43") (pinfunction "22_43") (pintype "passive"))
      (node (ref "P9") (pin "44") (pinfunction "47_44") (pintype "passive"))
      (node (ref "P9") (pin "45") (pinfunction "23_45") (pintype "passive"))
      (node (ref "P9") (pin "46") (pinfunction "48_46") (pintype "passive"))
      (node (ref "PMDC") (pin "3") (pinfunction "3_3") (pintype "passive"))
      (node (ref "TMP_4C") (pin "3") (pinfunction "A1_3") (pintype "passive"))
      (node (ref "TMP_4C") (pin "4") (pinfunction "A0_4") (pintype "passive"))
      (node (ref "TMP_4C") (pin "5") (pinfunction "GND_5") (pintype "power_in"))
    )
    (net (code "65") (name "V3_3D") (class "Default")
      (node (ref "C10") (pin "2") (pinfunction "2_2") (pintype "passive"))
      (node (ref "C11") (pin "2") (pinfunction "2_2") (pintype "passive"))
      (node (ref "C14") (pin "2") (pinfunction "2_2") (pintype "passive"))
      (node (ref "C15") (pin "2") (pinfunction "2_2") (pintype "passive"))
      (node (ref "C18") (pin "2") (pinfunction "2_2") (pintype "passive"))
      (node (ref "C19") (pin "2") (pinfunction "2_2") (pintype "passive"))
      (node (ref "C2") (pin "2") (pinfunction "2_2") (pintype "passive"))
      (node (ref "C22") (pin "2") (pinfunction "2_2") (pintype "passive"))
      (node (ref "C23") (pin "2") (pinfunction "2_2") (pintype "passive"))
      (node (ref "C26") (pin "2") (pinfunction "2_2") (pintype "passive"))
      (node (ref "C27") (pin "2") (pinfunction "2_2") (pintype "passive"))
      (node (ref "C3") (pin "2") (pinfunction "2_2") (pintype "passive"))
      (node (ref "C30") (pin "2") (pinfunction "2_2") (pintype "passive"))
      (node (ref "C31") (pin "2") (pinfunction "2_2") (pintype "passive"))
      (node (ref "C34") (pin "2") (pinfunction "2_2") (pintype "passive"))
      (node (ref "C35") (pin "2") (pinfunction "2_2") (pintype "passive"))
      (node (ref "C38") (pin "2") (pinfunction "2_2") (pintype "passive"))
      (node (ref "C39") (pin "2") (pinfunction "2_2") (pintype "passive"))
      (node (ref "C42") (pin "2") (pinfunction "2_2") (pintype "passive"))
      (node (ref "C43") (pin "2") (pinfunction "2_2") (pintype "passive"))
      (node (ref "C46") (pin "2") (pinfunction "2_2") (pintype "passive"))
      (node (ref "C47") (pin "2") (pinfunction "2_2") (pintype "passive"))
      (node (ref "C50") (pin "2") (pinfunction "2_2") (pintype "passive"))
      (node (ref "C51") (pin "2") (pinfunction "2_2") (pintype "passive"))
      (node (ref "C6") (pin "2") (pinfunction "2_2") (pintype "passive"))
      (node (ref "C7") (pin "2") (pinfunction "2_2") (pintype "passive"))
      (node (ref "C70") (pin "2") (pinfunction "2_2") (pintype "passive"))
      (node (ref "C71") (pin "2") (pinfunction "2_2") (pintype "passive"))
      (node (ref "INA_42") (pin "6") (pinfunction "VS_6") (pintype "passive"))
      (node (ref "INA_43") (pin "6") (pinfunction "VS_6") (pintype "passive"))
      (node (ref "INA_44") (pin "1") (pinfunction "A1_1") (pintype "passive"))
      (node (ref "INA_44") (pin "6") (pinfunction "VS_6") (pintype "passive"))
      (node (ref "INA_45") (pin "1") (pinfunction "A1_1") (pintype "passive"))
      (node (ref "INA_45") (pin "2") (pinfunction "A0_2") (pintype "passive"))
      (node (ref "INA_45") (pin "6") (pinfunction "VS_6") (pintype "passive"))
      (node (ref "INA_46") (pin "1") (pinfunction "A1_1") (pintype "passive"))
      (node (ref "INA_46") (pin "6") (pinfunction "VS_6") (pintype "passive"))
      (node (ref "INA_47") (pin "1") (pinfunction "A1_1") (pintype "passive"))
      (node (ref "INA_47") (pin "6") (pinfunction "VS_6") (pintype "passive"))
      (node (ref "INA_48") (pin "6") (pinfunction "VS_6") (pintype "passive"))
      (node (ref "INA_49") (pin "2") (pinfunction "A0_2") (pintype "passive"))
      (node (ref "INA_49") (pin "6") (pinfunction "VS_6") (pintype "passive"))
      (node (ref "INA_4A") (pin "6") (pinfunction "VS_6") (pintype "passive"))
      (node (ref "INA_4B") (pin "6") (pinfunction "VS_6") (pintype "passive"))
      (node (ref "INA_4D") (pin "2") (pinfunction "A0_2") (pintype "passive"))
      (node (ref "INA_4D") (pin "6") (pinfunction "VS_6") (pintype "passive"))
      (node (ref "INA_4E") (pin "6") (pinfunction "VS_6") (pintype "passive"))
      (node (ref "INA_4F") (pin "6") (pinfunction "VS_6") (pintype "passive"))
      (node (ref "LCD") (pin "38") (pinfunction "LED-A_38") (pintype "passive"))
      (node (ref "LCD") (pin "7") (pinfunction "VDD_7") (pintype "passive"))
      (node (ref "LCD") (pin "8") (pinfunction "IOVDD_8") (pintype "passive"))
      (node (ref "P9") (pin "3") (pinfunction "2_3") (pintype "passive"))
      (node (ref "P9") (pin "4") (pinfunction "27_4") (pintype "passive"))
      (node (ref "PMDC") (pin "5") (pinfunction "5_5") (pintype "passive"))
      (node (ref "R3") (pin "2") (pinfunction "2_2") (pintype "passive"))
      (node (ref "R4") (pin "2") (pinfunction "2_2") (pintype "passive"))
      (node (ref "TMP_4C") (pin "8") (pinfunction "V+_8") (pintype "power_in"))
    )
    (net (code "66") (name "unconnected-(INA_4A-Alert-Pad3)") (class "Default")
      (node (ref "INA_4A") (pin "3") (pinfunction "Alert_3") (pintype "passive"))
    )
    (net (code "67") (name "unconnected-(INA_4B-Alert-Pad3)") (class "Default")
      (node (ref "INA_4B") (pin "3") (pinfunction "Alert_3") (pintype "passive"))
    )
    (net (code "68") (name "unconnected-(INA_4D-Alert-Pad3)") (class "Default")
      (node (ref "INA_4D") (pin "3") (pinfunction "Alert_3") (pintype "passive"))
    )
    (net (code "69") (name "unconnected-(INA_4E-Alert-Pad3)") (class "Default")
      (node (ref "INA_4E") (pin "3") (pinfunction "Alert_3") (pintype "passive"))
    )
    (net (code "70") (name "unconnected-(INA_4F-Alert-Pad3)") (class "Default")
      (node (ref "INA_4F") (pin "3") (pinfunction "Alert_3") (pintype "passive"))
    )
    (net (code "71") (name "unconnected-(INA_42-Alert-Pad3)") (class "Default")
      (node (ref "INA_42") (pin "3") (pinfunction "Alert_3") (pintype "passive"))
    )
    (net (code "72") (name "unconnected-(INA_43-Alert-Pad3)") (class "Default")
      (node (ref "INA_43") (pin "3") (pinfunction "Alert_3") (pintype "passive"))
    )
    (net (code "73") (name "unconnected-(INA_44-Alert-Pad3)") (class "Default")
      (node (ref "INA_44") (pin "3") (pinfunction "Alert_3") (pintype "passive"))
    )
    (net (code "74") (name "unconnected-(INA_45-Alert-Pad3)") (class "Default")
      (node (ref "INA_45") (pin "3") (pinfunction "Alert_3") (pintype "passive"))
    )
    (net (code "75") (name "unconnected-(INA_46-Alert-Pad3)") (class "Default")
      (node (ref "INA_46") (pin "3") (pinfunction "Alert_3") (pintype "passive"))
    )
    (net (code "76") (name "unconnected-(INA_47-Alert-Pad3)") (class "Default")
      (node (ref "INA_47") (pin "3") (pinfunction "Alert_3") (pintype "passive"))
    )
    (net (code "77") (name "unconnected-(INA_48-Alert-Pad3)") (class "Default")
      (node (ref "INA_48") (pin "3") (pinfunction "Alert_3") (pintype "passive"))
    )
    (net (code "78") (name "unconnected-(INA_49-Alert-Pad3)") (class "Default")
      (node (ref "INA_49") (pin "3") (pinfunction "Alert_3") (pintype "passive"))
    )
    (net (code "79") (name "unconnected-(J1-Pad2)") (class "Default")
      (node (ref "J1") (pin "2") (pinfunction "2_2") (pintype "passive"))
    )
    (net (code "80") (name "unconnected-(J1-Pad3)") (class "Default")
      (node (ref "J1") (pin "3") (pinfunction "3_3") (pintype "passive"))
    )
    (net (code "81") (name "unconnected-(J1-Pad6)") (class "Default")
      (node (ref "J1") (pin "6") (pinfunction "6_6") (pintype "passive"))
    )
    (net (code "82") (name "unconnected-(LCD-IM0-Pad31)") (class "Default")
      (node (ref "LCD") (pin "31") (pinfunction "IM0_31") (pintype "passive"))
    )
    (net (code "83") (name "unconnected-(LCD-NC-Pad6)") (class "Default")
      (node (ref "LCD") (pin "6") (pinfunction "NC_6") (pintype "passive"))
    )
    (net (code "84") (name "unconnected-(LCD-NC-Pad9)") (class "Default")
      (node (ref "LCD") (pin "9") (pinfunction "NC_9") (pintype "passive"))
    )
    (net (code "85") (name "unconnected-(LCD-NC-Pad32)") (class "Default")
      (node (ref "LCD") (pin "32") (pinfunction "NC_32") (pintype "passive"))
    )
    (net (code "86") (name "unconnected-(LCD-NC-Pad40)") (class "Default")
      (node (ref "LCD") (pin "40") (pinfunction "NC_40") (pintype "passive"))
    )
    (net (code "87") (name "unconnected-(P8-2-Pad3)") (class "Default")
      (node (ref "P8") (pin "3") (pinfunction "2_3") (pintype "passive"))
    )
    (net (code "88") (name "unconnected-(P8-3-Pad5)") (class "Default")
      (node (ref "P8") (pin "5") (pinfunction "3_5") (pintype "passive"))
    )
    (net (code "89") (name "unconnected-(P8-4-Pad7)") (class "Default")
      (node (ref "P8") (pin "7") (pinfunction "4_7") (pintype "passive"))
    )
    (net (code "90") (name "unconnected-(P8-5-Pad9)") (class "Default")
      (node (ref "P8") (pin "9") (pinfunction "5_9") (pintype "passive"))
    )
    (net (code "91") (name "unconnected-(P8-6-Pad11)") (class "Default")
      (node (ref "P8") (pin "11") (pinfunction "6_11") (pintype "passive"))
    )
    (net (code "92") (name "unconnected-(P8-7-Pad13)") (class "Default")
      (node (ref "P8") (pin "13") (pinfunction "7_13") (pintype "passive"))
    )
    (net (code "93") (name "unconnected-(P8-8-Pad15)") (class "Default")
      (node (ref "P8") (pin "15") (pinfunction "8_15") (pintype "passive"))
    )
    (net (code "94") (name "unconnected-(P8-9-Pad17)") (class "Default")
      (node (ref "P8") (pin "17") (pinfunction "9_17") (pintype "passive"))
    )
    (net (code "95") (name "unconnected-(P8-10-Pad19)") (class "Default")
      (node (ref "P8") (pin "19") (pinfunction "10_19") (pintype "passive"))
    )
    (net (code "96") (name "unconnected-(P8-11-Pad21)") (class "Default")
      (node (ref "P8") (pin "21") (pinfunction "11_21") (pintype "passive"))
    )
    (net (code "97") (name "unconnected-(P8-12-Pad23)") (class "Default")
      (node (ref "P8") (pin "23") (pinfunction "12_23") (pintype "passive"))
    )
    (net (code "98") (name "unconnected-(P8-13-Pad25)") (class "Default")
      (node (ref "P8") (pin "25") (pinfunction "13_25") (pintype "passive"))
    )
    (net (code "99") (name "unconnected-(P8-27-Pad4)") (class "Default")
      (node (ref "P8") (pin "4") (pinfunction "27_4") (pintype "passive"))
    )
    (net (code "100") (name "unconnected-(P8-28-Pad6)") (class "Default")
      (node (ref "P8") (pin "6") (pinfunction "28_6") (pintype "passive"))
    )
    (net (code "101") (name "unconnected-(P8-29-Pad8)") (class "Default")
      (node (ref "P8") (pin "8") (pinfunction "29_8") (pintype "passive"))
    )
    (net (code "102") (name "unconnected-(P8-30-Pad10)") (class "Default")
      (node (ref "P8") (pin "10") (pinfunction "30_10") (pintype "passive"))
    )
    (net (code "103") (name "unconnected-(P8-32-Pad14)") (class "Default")
      (node (ref "P8") (pin "14") (pinfunction "32_14") (pintype "passive"))
    )
    (net (code "104") (name "unconnected-(P8-33-Pad16)") (class "Default")
      (node (ref "P8") (pin "16") (pinfunction "33_16") (pintype "passive"))
    )
    (net (code "105") (name "unconnected-(P8-34-Pad18)") (class "Default")
      (node (ref "P8") (pin "18") (pinfunction "34_18") (pintype "passive"))
    )
    (net (code "106") (name "unconnected-(P8-35-Pad20)") (class "Default")
      (node (ref "P8") (pin "20") (pinfunction "35_20") (pintype "passive"))
    )
    (net (code "107") (name "unconnected-(P8-36-Pad22)") (class "Default")
      (node (ref "P8") (pin "22") (pinfunction "36_22") (pintype "passive"))
    )
    (net (code "108") (name "unconnected-(P8-37-Pad24)") (class "Default")
      (node (ref "P8") (pin "24") (pinfunction "37_24") (pintype "passive"))
    )
    (net (code "109") (name "unconnected-(P8-38-Pad26)") (class "Default")
      (node (ref "P8") (pin "26") (pinfunction "38_26") (pintype "passive"))
    )
    (net (code "110") (name "unconnected-(P8-40-Pad30)") (class "Default")
      (node (ref "P8") (pin "30") (pinfunction "40_30") (pintype "passive"))
    )
    (net (code "111") (name "unconnected-(P9-3-Pad5)") (class "Default")
      (node (ref "P9") (pin "5") (pinfunction "3_5") (pintype "passive"))
    )
    (net (code "112") (name "unconnected-(P9-4-Pad7)") (class "Default")
      (node (ref "P9") (pin "7") (pinfunction "4_7") (pintype "passive"))
    )
    (net (code "113") (name "unconnected-(P9-5-Pad9)") (class "Default")
      (node (ref "P9") (pin "9") (pinfunction "5_9") (pintype "passive"))
    )
    (net (code "114") (name "unconnected-(P9-6-Pad11)") (class "Default")
      (node (ref "P9") (pin "11") (pinfunction "6_11") (pintype "passive"))
    )
    (net (code "115") (name "unconnected-(P9-7-Pad13)") (class "Default")
      (node (ref "P9") (pin "13") (pinfunction "7_13") (pintype "passive"))
    )
    (net (code "116") (name "unconnected-(P9-8-Pad15)") (class "Default")
      (node (ref "P9") (pin "15") (pinfunction "8_15") (pintype "passive"))
    )
    (net (code "117") (name "unconnected-(P9-11-Pad21)") (class "Default")
      (node (ref "P9") (pin "21") (pinfunction "11_21") (pintype "passive"))
    )
    (net (code "118") (name "unconnected-(P9-13-Pad25)") (class "Default")
      (node (ref "P9") (pin "25") (pinfunction "13_25") (pintype "passive"))
    )
    (net (code "119") (name "unconnected-(P9-15-Pad29)") (class "Default")
      (node (ref "P9") (pin "29") (pinfunction "15_29") (pintype "passive"))
    )
    (net (code "120") (name "unconnected-(P9-16-Pad31)") (class "Default")
      (node (ref "P9") (pin "31") (pinfunction "16_31") (pintype "passive"))
    )
    (net (code "121") (name "unconnected-(P9-17-Pad33)") (class "Default")
      (node (ref "P9") (pin "33") (pinfunction "17_33") (pintype "passive"))
    )
    (net (code "122") (name "unconnected-(P9-18-Pad35)") (class "Default")
      (node (ref "P9") (pin "35") (pinfunction "18_35") (pintype "passive"))
    )
    (net (code "123") (name "unconnected-(P9-21-Pad41)") (class "Default")
      (node (ref "P9") (pin "41") (pinfunction "21_41") (pintype "passive"))
    )
    (net (code "124") (name "unconnected-(P9-28-Pad6)") (class "Default")
      (node (ref "P9") (pin "6") (pinfunction "28_6") (pintype "passive"))
    )
    (net (code "125") (name "unconnected-(P9-29-Pad8)") (class "Default")
      (node (ref "P9") (pin "8") (pinfunction "29_8") (pintype "passive"))
    )
    (net (code "126") (name "unconnected-(P9-32-Pad14)") (class "Default")
      (node (ref "P9") (pin "14") (pinfunction "32_14") (pintype "passive"))
    )
    (net (code "127") (name "unconnected-(P9-33-Pad16)") (class "Default")
      (node (ref "P9") (pin "16") (pinfunction "33_16") (pintype "passive"))
    )
    (net (code "128") (name "unconnected-(P9-36-Pad22)") (class "Default")
      (node (ref "P9") (pin "22") (pinfunction "36_22") (pintype "passive"))
    )
    (net (code "129") (name "unconnected-(P9-37-Pad24)") (class "Default")
      (node (ref "P9") (pin "24") (pinfunction "37_24") (pintype "passive"))
    )
    (net (code "130") (name "unconnected-(P9-38-Pad26)") (class "Default")
      (node (ref "P9") (pin "26") (pinfunction "38_26") (pintype "passive"))
    )
    (net (code "131") (name "unconnected-(P9-39-Pad28)") (class "Default")
      (node (ref "P9") (pin "28") (pinfunction "39_28") (pintype "passive"))
    )
    (net (code "132") (name "unconnected-(P9-40-Pad30)") (class "Default")
      (node (ref "P9") (pin "30") (pinfunction "40_30") (pintype "passive"))
    )
    (net (code "133") (name "unconnected-(P9-41-Pad32)") (class "Default")
      (node (ref "P9") (pin "32") (pinfunction "41_32") (pintype "passive"))
    )
    (net (code "134") (name "unconnected-(P9-42-Pad34)") (class "Default")
      (node (ref "P9") (pin "34") (pinfunction "42_34") (pintype "passive"))
    )
    (net (code "135") (name "unconnected-(P9-43-Pad36)") (class "Default")
      (node (ref "P9") (pin "36") (pinfunction "43_36") (pintype "passive"))
    )
    (net (code "136") (name "unconnected-(P9-46-Pad42)") (class "Default")
      (node (ref "P9") (pin "42") (pinfunction "46_42") (pintype "passive"))
    )
  )
)
